# dlms_v1.net
KiCad netlist of a schematic drawn in EAGLE
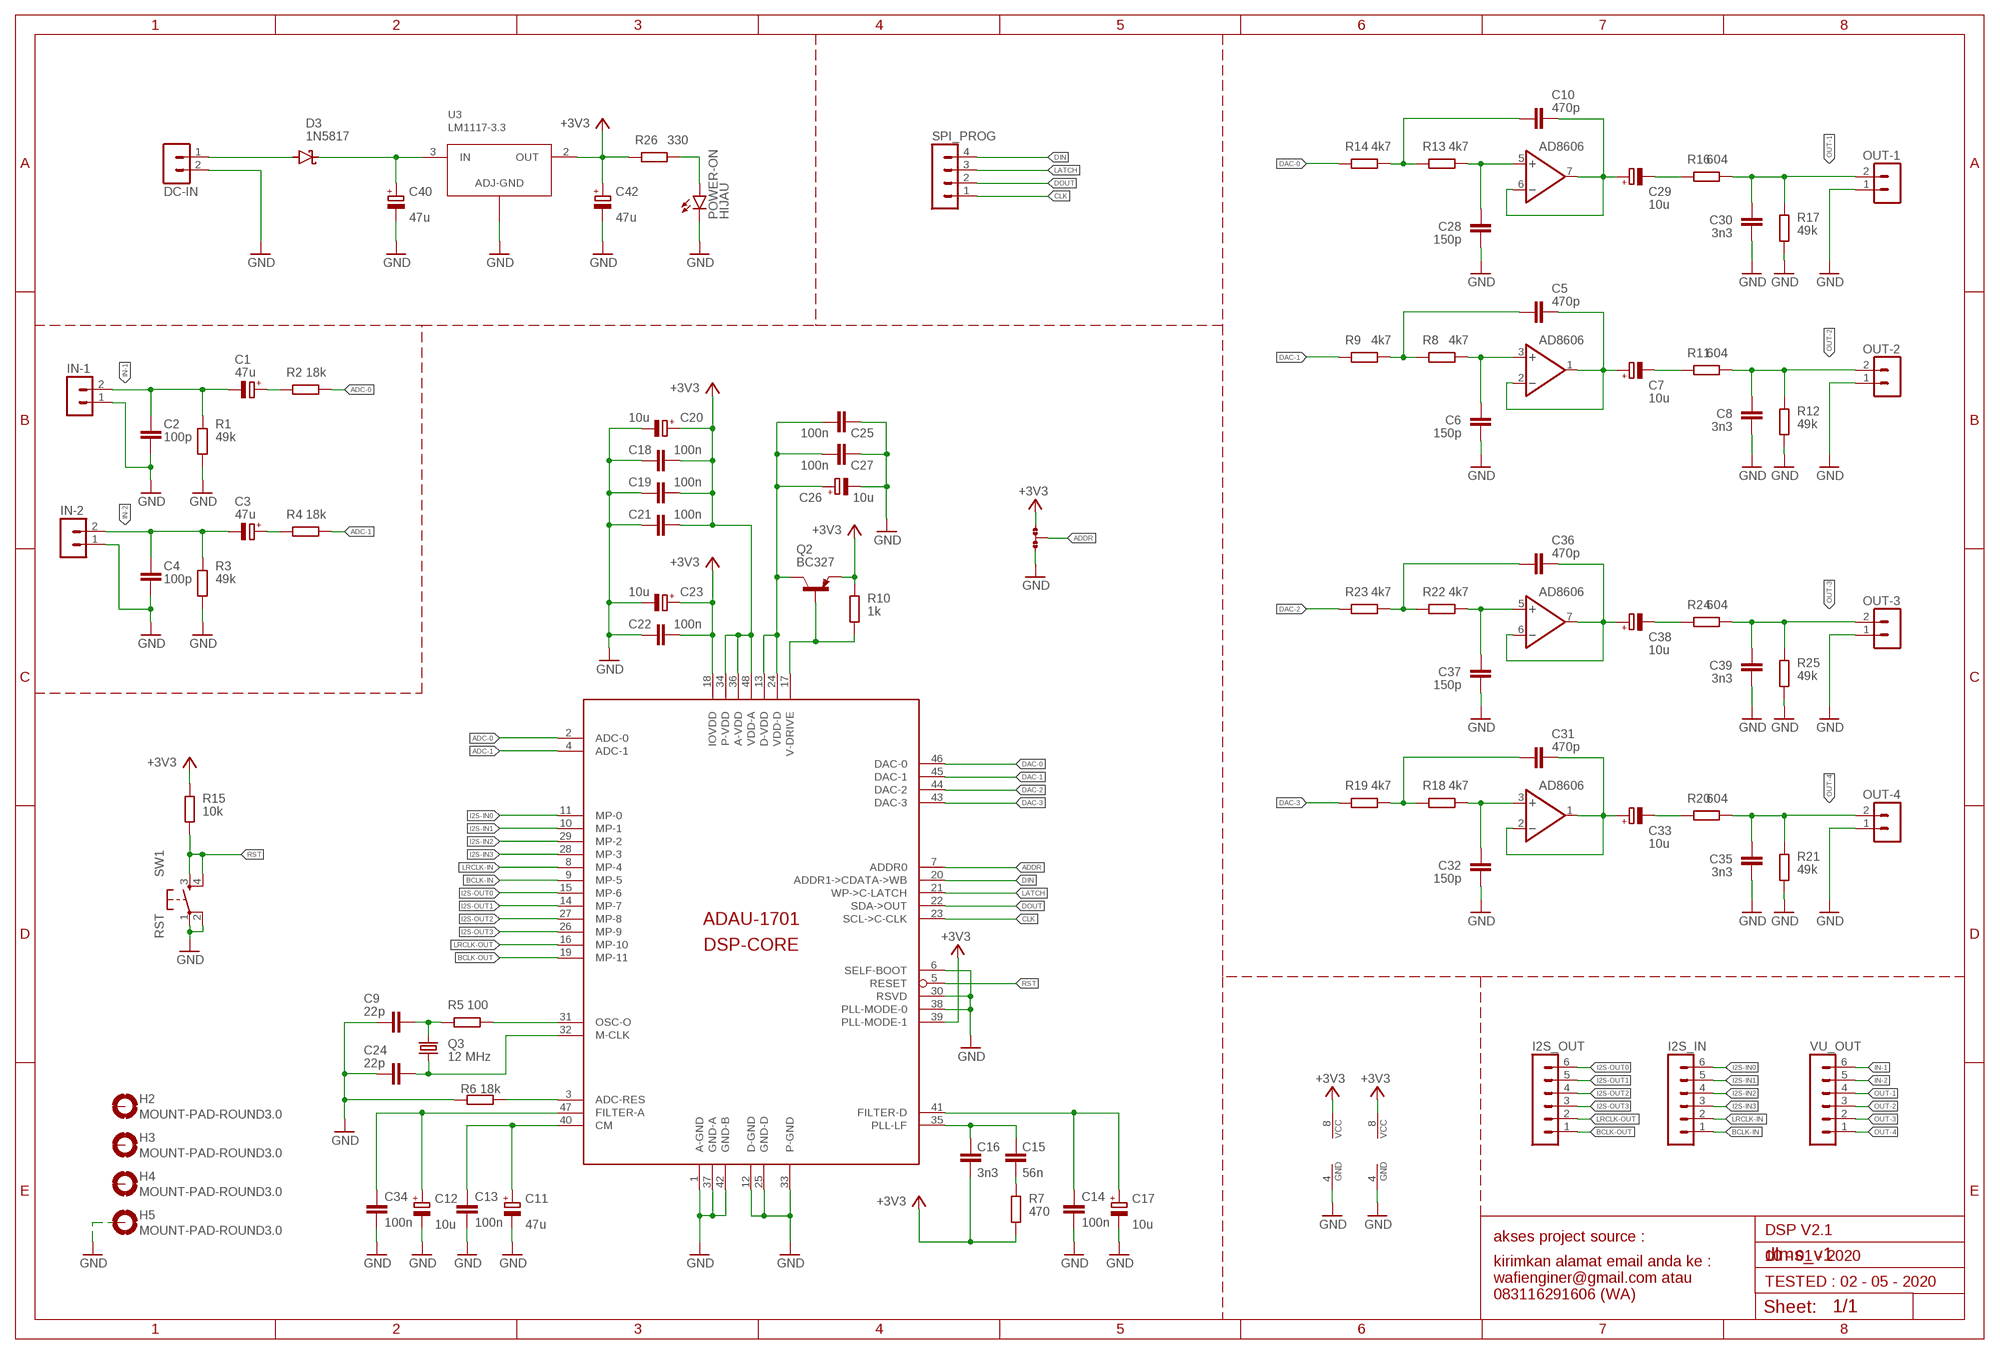
[diagram p0: schematic, sheet 1]

(export (version "E")
  (design (tool "Eeschema 10.0.6"))
  (components
    (comp (ref "ADDR")
      (value "0R-JUMPA")
      (footprint "eagle-import:A0R-JMP")
      (libsource (lib "eagle-import") (part "0R-JUMPA"))
    )
    (comp (ref "C1")
      (value "47u")
      (footprint "eagle-import:E2,5-5")
      (libsource (lib "eagle-import") (part "C10UF"))
    )
    (comp (ref "C2")
      (value "100p")
      (footprint "eagle-import:C050-024X044")
      (libsource (lib "eagle-import") (part "C-STD"))
    )
    (comp (ref "C3")
      (value "47u")
      (footprint "eagle-import:E2,5-5")
      (libsource (lib "eagle-import") (part "C10UF"))
    )
    (comp (ref "C4")
      (value "100p")
      (footprint "eagle-import:C050-024X044")
      (libsource (lib "eagle-import") (part "C-STD"))
    )
    (comp (ref "C5")
      (value "470p")
      (footprint "eagle-import:C050-024X044")
      (libsource (lib "eagle-import") (part "C-STD"))
    )
    (comp (ref "C6")
      (value "150p")
      (footprint "eagle-import:C050-024X044")
      (libsource (lib "eagle-import") (part "C-STD"))
    )
    (comp (ref "C7")
      (value "10u")
      (footprint "eagle-import:E2,5-5")
      (libsource (lib "eagle-import") (part "C10UF"))
    )
    (comp (ref "C8")
      (value "3n3")
      (footprint "eagle-import:C050-024X044")
      (libsource (lib "eagle-import") (part "C-STD"))
    )
    (comp (ref "C9")
      (value "22p")
      (footprint "eagle-import:0805")
      (libsource (lib "eagle-import") (part "CAP"))
    )
    (comp (ref "C10")
      (value "470p")
      (footprint "eagle-import:C050-024X044")
      (libsource (lib "eagle-import") (part "C-STD"))
    )
    (comp (ref "C11")
      (value "47u")
      (footprint "eagle-import:E2,5-5")
      (libsource (lib "eagle-import") (part "C10UF"))
    )
    (comp (ref "C12")
      (value "10u")
      (footprint "eagle-import:E2,5-5")
      (libsource (lib "eagle-import") (part "C10UF"))
    )
    (comp (ref "C13")
      (value "100n")
      (footprint "eagle-import:0805")
      (libsource (lib "eagle-import") (part "CAP"))
    )
    (comp (ref "C14")
      (value "100n")
      (footprint "eagle-import:0805")
      (libsource (lib "eagle-import") (part "CAP"))
    )
    (comp (ref "C15")
      (value "56n")
      (footprint "eagle-import:C050-024X044")
      (libsource (lib "eagle-import") (part "C-STD"))
    )
    (comp (ref "C16")
      (value "3n3")
      (footprint "eagle-import:C050-024X044")
      (libsource (lib "eagle-import") (part "C-STD"))
    )
    (comp (ref "C17")
      (value "10u")
      (footprint "eagle-import:E2,5-5")
      (libsource (lib "eagle-import") (part "C10UF"))
    )
    (comp (ref "C18")
      (value "100n")
      (footprint "eagle-import:0805")
      (libsource (lib "eagle-import") (part "CAP"))
    )
    (comp (ref "C19")
      (value "100n")
      (footprint "eagle-import:0805")
      (libsource (lib "eagle-import") (part "CAP"))
    )
    (comp (ref "C20")
      (value "10u")
      (footprint "eagle-import:E2,5-5")
      (libsource (lib "eagle-import") (part "C10UF"))
    )
    (comp (ref "C21")
      (value "100n")
      (footprint "eagle-import:0805")
      (libsource (lib "eagle-import") (part "CAP"))
    )
    (comp (ref "C22")
      (value "100n")
      (footprint "eagle-import:0805")
      (libsource (lib "eagle-import") (part "CAP"))
    )
    (comp (ref "C23")
      (value "10u")
      (footprint "eagle-import:E2,5-5")
      (libsource (lib "eagle-import") (part "C10UF"))
    )
    (comp (ref "C24")
      (value "22p")
      (footprint "eagle-import:0805")
      (libsource (lib "eagle-import") (part "CAP"))
    )
    (comp (ref "C25")
      (value "100n")
      (footprint "eagle-import:0805")
      (libsource (lib "eagle-import") (part "CAP"))
    )
    (comp (ref "C26")
      (value "10u")
      (footprint "eagle-import:E2,5-5")
      (libsource (lib "eagle-import") (part "C10UF"))
    )
    (comp (ref "C27")
      (value "100n")
      (footprint "eagle-import:0805")
      (libsource (lib "eagle-import") (part "CAP"))
    )
    (comp (ref "C28")
      (value "150p")
      (footprint "eagle-import:C050-024X044")
      (libsource (lib "eagle-import") (part "C-STD"))
    )
    (comp (ref "C29")
      (value "10u")
      (footprint "eagle-import:E2,5-5")
      (libsource (lib "eagle-import") (part "C10UF"))
    )
    (comp (ref "C30")
      (value "3n3")
      (footprint "eagle-import:C050-024X044")
      (libsource (lib "eagle-import") (part "C-STD"))
    )
    (comp (ref "C31")
      (value "470p")
      (footprint "eagle-import:C050-024X044")
      (libsource (lib "eagle-import") (part "C-STD"))
    )
    (comp (ref "C32")
      (value "150p")
      (footprint "eagle-import:C050-024X044")
      (libsource (lib "eagle-import") (part "C-STD"))
    )
    (comp (ref "C33")
      (value "10u")
      (footprint "eagle-import:E2,5-5")
      (libsource (lib "eagle-import") (part "C10UF"))
    )
    (comp (ref "C34")
      (value "100n")
      (footprint "eagle-import:0805")
      (libsource (lib "eagle-import") (part "CAP"))
    )
    (comp (ref "C35")
      (value "3n3")
      (footprint "eagle-import:C050-024X044")
      (libsource (lib "eagle-import") (part "C-STD"))
    )
    (comp (ref "C36")
      (value "470p")
      (footprint "eagle-import:C050-024X044")
      (libsource (lib "eagle-import") (part "C-STD"))
    )
    (comp (ref "C37")
      (value "150p")
      (footprint "eagle-import:C050-024X044")
      (libsource (lib "eagle-import") (part "C-STD"))
    )
    (comp (ref "C38")
      (value "10u")
      (footprint "eagle-import:E2,5-5")
      (libsource (lib "eagle-import") (part "C10UF"))
    )
    (comp (ref "C39")
      (value "3n3")
      (footprint "eagle-import:C050-024X044")
      (libsource (lib "eagle-import") (part "C-STD"))
    )
    (comp (ref "C40")
      (value "47u")
      (footprint "eagle-import:E2,5-5")
      (libsource (lib "eagle-import") (part "C10UF"))
    )
    (comp (ref "C42")
      (value "47u")
      (footprint "eagle-import:E2,5-5")
      (libsource (lib "eagle-import") (part "C10UF"))
    )
    (comp (ref "D3")
      (value "1N5817")
      (footprint "eagle-import:DO35Z7")
      (libsource (lib "eagle-import") (part "1N5817"))
    )
    (comp (ref "DC-IN")
      (value "MOLEX-2")
      (footprint "eagle-import:6410-02")
      (libsource (lib "eagle-import") (part "MOLEX-2"))
    )
    (comp (ref "H2")
      (value "MOUNT-PAD-ROUND3.0")
      (footprint "eagle-import:3,0-PAD")
      (libsource (lib "eagle-import") (part "MOUNT-PAD-ROUND3.0"))
    )
    (comp (ref "H3")
      (value "MOUNT-PAD-ROUND3.0")
      (footprint "eagle-import:3,0-PAD")
      (libsource (lib "eagle-import") (part "MOUNT-PAD-ROUND3.0"))
    )
    (comp (ref "H4")
      (value "MOUNT-PAD-ROUND3.0")
      (footprint "eagle-import:3,0-PAD")
      (libsource (lib "eagle-import") (part "MOUNT-PAD-ROUND3.0"))
    )
    (comp (ref "H5")
      (value "MOUNT-PAD-ROUND3.0")
      (footprint "eagle-import:3,0-PAD")
      (libsource (lib "eagle-import") (part "MOUNT-PAD-ROUND3.0"))
    )
    (comp (ref "I2S_IN")
      (value "MOLEX-6")
      (footprint "eagle-import:6410-06")
      (libsource (lib "eagle-import") (part "MOLEX-6"))
    )
    (comp (ref "I2S_OUT")
      (value "MOLEX-6")
      (footprint "eagle-import:6410-06")
      (libsource (lib "eagle-import") (part "MOLEX-6"))
    )
    (comp (ref "IC1")
      (value "AD8606")
      (footprint "eagle-import:SOP8")
      (libsource (lib "eagle-import") (part "AD8606"))
    )
    (comp (ref "IC2")
      (value "AD8606")
      (footprint "eagle-import:SOP8")
      (libsource (lib "eagle-import") (part "AD8606"))
    )
    (comp (ref "IN-1")
      (value "MOLEX-2")
      (footprint "eagle-import:6410-02")
      (libsource (lib "eagle-import") (part "MOLEX-2"))
    )
    (comp (ref "IN-2")
      (value "MOLEX-2")
      (footprint "eagle-import:6410-02")
      (libsource (lib "eagle-import") (part "MOLEX-2"))
    )
    (comp (ref "OUT-1")
      (value "MOLEX-2")
      (footprint "eagle-import:6410-02")
      (libsource (lib "eagle-import") (part "MOLEX-2"))
    )
    (comp (ref "OUT-2")
      (value "MOLEX-2")
      (footprint "eagle-import:6410-02")
      (libsource (lib "eagle-import") (part "MOLEX-2"))
    )
    (comp (ref "OUT-3")
      (value "MOLEX-2")
      (footprint "eagle-import:6410-02")
      (libsource (lib "eagle-import") (part "MOLEX-2"))
    )
    (comp (ref "OUT-4")
      (value "MOLEX-2")
      (footprint "eagle-import:6410-02")
      (libsource (lib "eagle-import") (part "MOLEX-2"))
    )
    (comp (ref "POWER-ON")
      (value "HIJAU")
      (footprint "eagle-import:LED3MM")
      (libsource (lib "eagle-import") (part "LED3MM"))
    )
    (comp (ref "Q2")
      (value "BC327")
      (footprint "eagle-import:TO92-EBC")
      (libsource (lib "eagle-import") (part "BC327"))
    )
    (comp (ref "Q3")
      (value "12 MHz")
      (footprint "eagle-import:HC49UP")
      (libsource (lib "eagle-import") (part "CRYSTALHC49UP"))
    )
    (comp (ref "R1")
      (value "49k")
      (footprint "eagle-import:0204_7")
      (libsource (lib "eagle-import") (part "R025"))
    )
    (comp (ref "R2")
      (value "18k")
      (footprint "eagle-import:0204_7")
      (libsource (lib "eagle-import") (part "R025"))
    )
    (comp (ref "R3")
      (value "49k")
      (footprint "eagle-import:0204_7")
      (libsource (lib "eagle-import") (part "R025"))
    )
    (comp (ref "R4")
      (value "18k")
      (footprint "eagle-import:0204_7")
      (libsource (lib "eagle-import") (part "R025"))
    )
    (comp (ref "R5")
      (value "100")
      (footprint "eagle-import:0204_7")
      (libsource (lib "eagle-import") (part "R025"))
    )
    (comp (ref "R6")
      (value "18k")
      (footprint "eagle-import:0204_7")
      (libsource (lib "eagle-import") (part "R025"))
    )
    (comp (ref "R7")
      (value "470")
      (footprint "eagle-import:0204_7")
      (libsource (lib "eagle-import") (part "R025"))
    )
    (comp (ref "R8")
      (value "4k7")
      (footprint "eagle-import:0204_7")
      (libsource (lib "eagle-import") (part "R025"))
    )
    (comp (ref "R9")
      (value "4k7")
      (footprint "eagle-import:0204_7")
      (libsource (lib "eagle-import") (part "R025"))
    )
    (comp (ref "R10")
      (value "1k")
      (footprint "eagle-import:0204_7")
      (libsource (lib "eagle-import") (part "R025"))
    )
    (comp (ref "R11")
      (value "604")
      (footprint "eagle-import:0204_7")
      (libsource (lib "eagle-import") (part "R025"))
    )
    (comp (ref "R12")
      (value "49k")
      (footprint "eagle-import:0204_7")
      (libsource (lib "eagle-import") (part "R025"))
    )
    (comp (ref "R13")
      (value "4k7")
      (footprint "eagle-import:0204_7")
      (libsource (lib "eagle-import") (part "R025"))
    )
    (comp (ref "R14")
      (value "4k7")
      (footprint "eagle-import:0204_7")
      (libsource (lib "eagle-import") (part "R025"))
    )
    (comp (ref "R15")
      (value "10k")
      (footprint "eagle-import:0204_7")
      (libsource (lib "eagle-import") (part "R025"))
    )
    (comp (ref "R16")
      (value "604")
      (footprint "eagle-import:0204_7")
      (libsource (lib "eagle-import") (part "R025"))
    )
    (comp (ref "R17")
      (value "49k")
      (footprint "eagle-import:0204_7")
      (libsource (lib "eagle-import") (part "R025"))
    )
    (comp (ref "R18")
      (value "4k7")
      (footprint "eagle-import:0204_7")
      (libsource (lib "eagle-import") (part "R025"))
    )
    (comp (ref "R19")
      (value "4k7")
      (footprint "eagle-import:0204_7")
      (libsource (lib "eagle-import") (part "R025"))
    )
    (comp (ref "R20")
      (value "604")
      (footprint "eagle-import:0204_7")
      (libsource (lib "eagle-import") (part "R025"))
    )
    (comp (ref "R21")
      (value "49k")
      (footprint "eagle-import:0204_7")
      (libsource (lib "eagle-import") (part "R025"))
    )
    (comp (ref "R22")
      (value "4k7")
      (footprint "eagle-import:0204_7")
      (libsource (lib "eagle-import") (part "R025"))
    )
    (comp (ref "R23")
      (value "4k7")
      (footprint "eagle-import:0204_7")
      (libsource (lib "eagle-import") (part "R025"))
    )
    (comp (ref "R24")
      (value "604")
      (footprint "eagle-import:0204_7")
      (libsource (lib "eagle-import") (part "R025"))
    )
    (comp (ref "R25")
      (value "49k")
      (footprint "eagle-import:0204_7")
      (libsource (lib "eagle-import") (part "R025"))
    )
    (comp (ref "R26")
      (value "330")
      (footprint "eagle-import:0204_7")
      (libsource (lib "eagle-import") (part "R025"))
    )
    (comp (ref "RST")
      (value "SW1")
      (footprint "eagle-import:B3F-10XX")
      (libsource (lib "eagle-import") (part "SW"))
    )
    (comp (ref "SPI_PROG")
      (value "MOLEX-4")
      (footprint "eagle-import:6410-04")
      (libsource (lib "eagle-import") (part "MOLEX-4"))
    )
    (comp (ref "U1")
      (value "ADAU-1701")
      (footprint "eagle-import:LQFP-48")
      (libsource (lib "eagle-import") (part "ADAU-1701"))
    )
    (comp (ref "U3")
      (value "LM1117-3.3")
      (footprint "eagle-import:TO220H")
      (libsource (lib "eagle-import") (part "LM1117-3.3"))
    )
    (comp (ref "VU_OUT")
      (value "MOLEX-6")
      (footprint "eagle-import:6410-06")
      (libsource (lib "eagle-import") (part "MOLEX-6"))
    )
  )
  (nets
    (net (code "1") (name "+3V3") (class "Default")
      (node (ref "ADDR") (pin "1") (pinfunction "1_1") (pintype "passive"))
      (node (ref "C16") (pin "2") (pinfunction "2_2") (pintype "passive"))
      (node (ref "C18") (pin "P$1") (pinfunction "1_P$1") (pintype "passive"))
      (node (ref "C19") (pin "P$1") (pinfunction "1_P$1") (pintype "passive"))
      (node (ref "C20") (pin "+") (pinfunction "+_+") (pintype "passive"))
      (node (ref "C21") (pin "P$1") (pinfunction "1_P$1") (pintype "passive"))
      (node (ref "C22") (pin "P$1") (pinfunction "1_P$1") (pintype "passive"))
      (node (ref "C23") (pin "+") (pinfunction "+_+") (pintype "passive"))
      (node (ref "C42") (pin "+") (pinfunction "+_+") (pintype "passive"))
      (node (ref "IC1") (pin "8") (pinfunction "VCC_8") (pintype "power_in"))
      (node (ref "IC2") (pin "8") (pinfunction "VCC_8") (pintype "power_in"))
      (node (ref "Q2") (pin "E") (pinfunction "E_E") (pintype "passive"))
      (node (ref "R10") (pin "2") (pinfunction "2_2") (pintype "passive"))
      (node (ref "R15") (pin "2") (pinfunction "2_2") (pintype "passive"))
      (node (ref "R26") (pin "1") (pinfunction "1_1") (pintype "passive"))
      (node (ref "R7") (pin "1") (pinfunction "1_1") (pintype "passive"))
      (node (ref "U1") (pin "18") (pinfunction "IOVDD_18") (pintype "bidirectional"))
      (node (ref "U1") (pin "34") (pinfunction "P-VDD_34") (pintype "bidirectional"))
      (node (ref "U1") (pin "36") (pinfunction "A-VDD_36") (pintype "bidirectional"))
      (node (ref "U1") (pin "39") (pinfunction "PLL-MODE-1_39") (pintype "bidirectional"))
      (node (ref "U1") (pin "48") (pinfunction "VDD-A_48") (pintype "bidirectional"))
      (node (ref "U3") (pin "2") (pinfunction "OUT_2") (pintype "bidirectional"))
    )
    (net (code "2") (name "ADC-0") (class "Default")
      (node (ref "R2") (pin "2") (pinfunction "2_2") (pintype "passive"))
      (node (ref "U1") (pin "2") (pinfunction "ADC-0_2") (pintype "bidirectional"))
    )
    (net (code "3") (name "ADC-1") (class "Default")
      (node (ref "R4") (pin "2") (pinfunction "2_2") (pintype "passive"))
      (node (ref "U1") (pin "4") (pinfunction "ADC-1_4") (pintype "bidirectional"))
    )
    (net (code "4") (name "ADDR") (class "Default")
      (node (ref "ADDR") (pin "2") (pinfunction "2_2") (pintype "passive"))
      (node (ref "U1") (pin "7") (pinfunction "ADDR0_7") (pintype "bidirectional"))
    )
    (net (code "5") (name "BCLK-IN") (class "Default")
      (node (ref "I2S_IN") (pin "1") (pinfunction "1_1") (pintype "passive"))
      (node (ref "U1") (pin "9") (pinfunction "MP-5_9") (pintype "bidirectional"))
    )
    (net (code "6") (name "BCLK-OUT") (class "Default")
      (node (ref "I2S_OUT") (pin "1") (pinfunction "1_1") (pintype "passive"))
      (node (ref "U1") (pin "19") (pinfunction "MP-11_19") (pintype "bidirectional"))
    )
    (net (code "7") (name "CLK") (class "Default")
      (node (ref "SPI_PROG") (pin "1") (pinfunction "1_1") (pintype "passive"))
      (node (ref "U1") (pin "23") (pinfunction "SCL->C-CLK_23") (pintype "bidirectional"))
    )
    (net (code "8") (name "DAC-0") (class "Default")
      (node (ref "R14") (pin "1") (pinfunction "1_1") (pintype "passive"))
      (node (ref "U1") (pin "46") (pinfunction "DAC-0_46") (pintype "bidirectional"))
    )
    (net (code "9") (name "DAC-1") (class "Default")
      (node (ref "R9") (pin "1") (pinfunction "1_1") (pintype "passive"))
      (node (ref "U1") (pin "45") (pinfunction "DAC-1_45") (pintype "bidirectional"))
    )
    (net (code "10") (name "DAC-2") (class "Default")
      (node (ref "R23") (pin "1") (pinfunction "1_1") (pintype "passive"))
      (node (ref "U1") (pin "44") (pinfunction "DAC-2_44") (pintype "bidirectional"))
    )
    (net (code "11") (name "DAC-3") (class "Default")
      (node (ref "R19") (pin "1") (pinfunction "1_1") (pintype "passive"))
      (node (ref "U1") (pin "43") (pinfunction "DAC-3_43") (pintype "bidirectional"))
    )
    (net (code "12") (name "DIN") (class "Default")
      (node (ref "SPI_PROG") (pin "4") (pinfunction "4_4") (pintype "passive"))
      (node (ref "U1") (pin "20") (pinfunction "ADDR1->CDATA->WB_20") (pintype "bidirectional"))
    )
    (net (code "13") (name "DOUT") (class "Default")
      (node (ref "SPI_PROG") (pin "2") (pinfunction "2_2") (pintype "passive"))
      (node (ref "U1") (pin "22") (pinfunction "SDA->OUT_22") (pintype "bidirectional"))
    )
    (net (code "14") (name "GND") (class "Default")
      (node (ref "ADDR") (pin "3") (pinfunction "3_3") (pintype "passive"))
      (node (ref "C11") (pin "-") (pinfunction "-_-") (pintype "passive"))
      (node (ref "C12") (pin "-") (pinfunction "-_-") (pintype "passive"))
      (node (ref "C13") (pin "P$2") (pinfunction "2_P$2") (pintype "passive"))
      (node (ref "C14") (pin "P$2") (pinfunction "2_P$2") (pintype "passive"))
      (node (ref "C17") (pin "-") (pinfunction "-_-") (pintype "passive"))
      (node (ref "C18") (pin "P$2") (pinfunction "2_P$2") (pintype "passive"))
      (node (ref "C19") (pin "P$2") (pinfunction "2_P$2") (pintype "passive"))
      (node (ref "C2") (pin "2") (pinfunction "2_2") (pintype "passive"))
      (node (ref "C20") (pin "-") (pinfunction "-_-") (pintype "passive"))
      (node (ref "C21") (pin "P$2") (pinfunction "2_P$2") (pintype "passive"))
      (node (ref "C22") (pin "P$2") (pinfunction "2_P$2") (pintype "passive"))
      (node (ref "C23") (pin "-") (pinfunction "-_-") (pintype "passive"))
      (node (ref "C24") (pin "P$2") (pinfunction "2_P$2") (pintype "passive"))
      (node (ref "C25") (pin "P$2") (pinfunction "2_P$2") (pintype "passive"))
      (node (ref "C26") (pin "-") (pinfunction "-_-") (pintype "passive"))
      (node (ref "C27") (pin "P$2") (pinfunction "2_P$2") (pintype "passive"))
      (node (ref "C28") (pin "1") (pinfunction "1_1") (pintype "passive"))
      (node (ref "C30") (pin "2") (pinfunction "2_2") (pintype "passive"))
      (node (ref "C32") (pin "1") (pinfunction "1_1") (pintype "passive"))
      (node (ref "C34") (pin "P$2") (pinfunction "2_P$2") (pintype "passive"))
      (node (ref "C35") (pin "2") (pinfunction "2_2") (pintype "passive"))
      (node (ref "C37") (pin "1") (pinfunction "1_1") (pintype "passive"))
      (node (ref "C39") (pin "2") (pinfunction "2_2") (pintype "passive"))
      (node (ref "C4") (pin "2") (pinfunction "2_2") (pintype "passive"))
      (node (ref "C40") (pin "-") (pinfunction "-_-") (pintype "passive"))
      (node (ref "C42") (pin "-") (pinfunction "-_-") (pintype "passive"))
      (node (ref "C6") (pin "1") (pinfunction "1_1") (pintype "passive"))
      (node (ref "C8") (pin "2") (pinfunction "2_2") (pintype "passive"))
      (node (ref "C9") (pin "P$2") (pinfunction "2_P$2") (pintype "passive"))
      (node (ref "DC-IN") (pin "2") (pinfunction "2_2") (pintype "passive"))
      (node (ref "H5") (pin "B3,0") (pinfunction "MOUNT_B3,0") (pintype "passive"))
      (node (ref "IC1") (pin "4") (pinfunction "GND_4") (pintype "power_in"))
      (node (ref "IC2") (pin "4") (pinfunction "GND_4") (pintype "power_in"))
      (node (ref "IN-1") (pin "1") (pinfunction "1_1") (pintype "passive"))
      (node (ref "IN-2") (pin "1") (pinfunction "1_1") (pintype "passive"))
      (node (ref "OUT-1") (pin "1") (pinfunction "1_1") (pintype "passive"))
      (node (ref "OUT-2") (pin "1") (pinfunction "1_1") (pintype "passive"))
      (node (ref "OUT-3") (pin "1") (pinfunction "1_1") (pintype "passive"))
      (node (ref "OUT-4") (pin "1") (pinfunction "1_1") (pintype "passive"))
      (node (ref "POWER-ON") (pin "K") (pinfunction "C_K") (pintype "passive"))
      (node (ref "R1") (pin "1") (pinfunction "1_1") (pintype "passive"))
      (node (ref "R12") (pin "1") (pinfunction "1_1") (pintype "passive"))
      (node (ref "R17") (pin "1") (pinfunction "1_1") (pintype "passive"))
      (node (ref "R21") (pin "1") (pinfunction "1_1") (pintype "passive"))
      (node (ref "R25") (pin "1") (pinfunction "1_1") (pintype "passive"))
      (node (ref "R3") (pin "1") (pinfunction "1_1") (pintype "passive"))
      (node (ref "R6") (pin "1") (pinfunction "1_1") (pintype "passive"))
      (node (ref "RST") (pin "1") (pinfunction "P_1") (pintype "passive"))
      (node (ref "RST") (pin "2") (pinfunction "P1_2") (pintype "passive"))
      (node (ref "U1") (pin "1") (pinfunction "A-GND_1") (pintype "bidirectional"))
      (node (ref "U1") (pin "12") (pinfunction "D-GND_12") (pintype "bidirectional"))
      (node (ref "U1") (pin "25") (pinfunction "GND-D_25") (pintype "bidirectional"))
      (node (ref "U1") (pin "30") (pinfunction "RSVD_30") (pintype "bidirectional"))
      (node (ref "U1") (pin "33") (pinfunction "P-GND_33") (pintype "bidirectional"))
      (node (ref "U1") (pin "37") (pinfunction "GND-A_37") (pintype "bidirectional"))
      (node (ref "U1") (pin "38") (pinfunction "PLL-MODE-0_38") (pintype "bidirectional"))
      (node (ref "U1") (pin "42") (pinfunction "GND-B_42") (pintype "bidirectional"))
      (node (ref "U1") (pin "6") (pinfunction "SELF-BOOT_6") (pintype "bidirectional"))
      (node (ref "U3") (pin "1") (pinfunction "GND_1") (pintype "bidirectional"))
    )
    (net (code "15") (name "I2S-IN0") (class "Default")
      (node (ref "I2S_IN") (pin "6") (pinfunction "6_6") (pintype "passive"))
      (node (ref "U1") (pin "11") (pinfunction "MP-0_11") (pintype "bidirectional"))
    )
    (net (code "16") (name "I2S-IN1") (class "Default")
      (node (ref "I2S_IN") (pin "5") (pinfunction "5_5") (pintype "passive"))
      (node (ref "U1") (pin "10") (pinfunction "MP-1_10") (pintype "bidirectional"))
    )
    (net (code "17") (name "I2S-IN2") (class "Default")
      (node (ref "I2S_IN") (pin "4") (pinfunction "4_4") (pintype "passive"))
      (node (ref "U1") (pin "29") (pinfunction "MP-2_29") (pintype "bidirectional"))
    )
    (net (code "18") (name "I2S-IN3") (class "Default")
      (node (ref "I2S_IN") (pin "3") (pinfunction "3_3") (pintype "passive"))
      (node (ref "U1") (pin "28") (pinfunction "MP-3_28") (pintype "bidirectional"))
    )
    (net (code "19") (name "I2S-OUT0") (class "Default")
      (node (ref "I2S_OUT") (pin "6") (pinfunction "6_6") (pintype "passive"))
      (node (ref "U1") (pin "15") (pinfunction "MP-6_15") (pintype "bidirectional"))
    )
    (net (code "20") (name "I2S-OUT1") (class "Default")
      (node (ref "I2S_OUT") (pin "5") (pinfunction "5_5") (pintype "passive"))
      (node (ref "U1") (pin "14") (pinfunction "MP-7_14") (pintype "bidirectional"))
    )
    (net (code "21") (name "I2S-OUT2") (class "Default")
      (node (ref "I2S_OUT") (pin "4") (pinfunction "4_4") (pintype "passive"))
      (node (ref "U1") (pin "27") (pinfunction "MP-8_27") (pintype "bidirectional"))
    )
    (net (code "22") (name "I2S-OUT3") (class "Default")
      (node (ref "I2S_OUT") (pin "3") (pinfunction "3_3") (pintype "passive"))
      (node (ref "U1") (pin "26") (pinfunction "MP-9_26") (pintype "bidirectional"))
    )
    (net (code "23") (name "IN-1") (class "Default")
      (node (ref "C1") (pin "-") (pinfunction "-_-") (pintype "passive"))
      (node (ref "C2") (pin "1") (pinfunction "1_1") (pintype "passive"))
      (node (ref "IN-1") (pin "2") (pinfunction "2_2") (pintype "passive"))
      (node (ref "R1") (pin "2") (pinfunction "2_2") (pintype "passive"))
      (node (ref "VU_OUT") (pin "6") (pinfunction "6_6") (pintype "passive"))
    )
    (net (code "24") (name "IN-2") (class "Default")
      (node (ref "C3") (pin "-") (pinfunction "-_-") (pintype "passive"))
      (node (ref "C4") (pin "1") (pinfunction "1_1") (pintype "passive"))
      (node (ref "IN-2") (pin "2") (pinfunction "2_2") (pintype "passive"))
      (node (ref "R3") (pin "2") (pinfunction "2_2") (pintype "passive"))
      (node (ref "VU_OUT") (pin "5") (pinfunction "5_5") (pintype "passive"))
    )
    (net (code "25") (name "LATCH") (class "Default")
      (node (ref "SPI_PROG") (pin "3") (pinfunction "3_3") (pintype "passive"))
      (node (ref "U1") (pin "21") (pinfunction "WP->C-LATCH_21") (pintype "bidirectional"))
    )
    (net (code "26") (name "LRCLK-IN") (class "Default")
      (node (ref "I2S_IN") (pin "2") (pinfunction "2_2") (pintype "passive"))
      (node (ref "U1") (pin "8") (pinfunction "MP-4_8") (pintype "bidirectional"))
    )
    (net (code "27") (name "LRCLK-OUT") (class "Default")
      (node (ref "I2S_OUT") (pin "2") (pinfunction "2_2") (pintype "passive"))
      (node (ref "U1") (pin "16") (pinfunction "MP-10_16") (pintype "bidirectional"))
    )
    (net (code "28") (name "Net-(C1-Pad+)") (class "Default")
      (node (ref "C1") (pin "+") (pinfunction "+_+") (pintype "passive"))
      (node (ref "R2") (pin "1") (pinfunction "1_1") (pintype "passive"))
    )
    (net (code "29") (name "Net-(C3-Pad+)") (class "Default")
      (node (ref "C3") (pin "+") (pinfunction "+_+") (pintype "passive"))
      (node (ref "R4") (pin "1") (pinfunction "1_1") (pintype "passive"))
    )
    (net (code "30") (name "Net-(C5-Pad1)") (class "Default")
      (node (ref "C5") (pin "1") (pinfunction "1_1") (pintype "passive"))
      (node (ref "R8") (pin "1") (pinfunction "1_1") (pintype "passive"))
      (node (ref "R9") (pin "2") (pinfunction "2_2") (pintype "passive"))
    )
    (net (code "31") (name "Net-(C7-Pad-)") (class "Default")
      (node (ref "C7") (pin "-") (pinfunction "-_-") (pintype "passive"))
      (node (ref "R11") (pin "1") (pinfunction "1_1") (pintype "passive"))
    )
    (net (code "32") (name "Net-(C9-1)") (class "Default")
      (node (ref "C9") (pin "P$1") (pinfunction "1_P$1") (pintype "passive"))
      (node (ref "Q3") (pin "2") (pinfunction "2_2") (pintype "passive"))
      (node (ref "R5") (pin "1") (pinfunction "1_1") (pintype "passive"))
    )
    (net (code "33") (name "Net-(C10-Pad1)") (class "Default")
      (node (ref "C10") (pin "1") (pinfunction "1_1") (pintype "passive"))
      (node (ref "R13") (pin "1") (pinfunction "1_1") (pintype "passive"))
      (node (ref "R14") (pin "2") (pinfunction "2_2") (pintype "passive"))
    )
    (net (code "34") (name "Net-(C13-1)") (class "Default")
      (node (ref "C11") (pin "+") (pinfunction "+_+") (pintype "passive"))
      (node (ref "C13") (pin "P$1") (pinfunction "1_P$1") (pintype "passive"))
      (node (ref "U1") (pin "40") (pinfunction "CM_40") (pintype "bidirectional"))
    )
    (net (code "35") (name "Net-(C14-1)") (class "Default")
      (node (ref "C14") (pin "P$1") (pinfunction "1_P$1") (pintype "passive"))
      (node (ref "C17") (pin "+") (pinfunction "+_+") (pintype "passive"))
      (node (ref "U1") (pin "41") (pinfunction "FILTER-D_41") (pintype "bidirectional"))
    )
    (net (code "36") (name "Net-(C15-Pad2)") (class "Default")
      (node (ref "C15") (pin "2") (pinfunction "2_2") (pintype "passive"))
      (node (ref "R7") (pin "2") (pinfunction "2_2") (pintype "passive"))
    )
    (net (code "37") (name "Net-(C24-1)") (class "Default")
      (node (ref "C24") (pin "P$1") (pinfunction "1_P$1") (pintype "passive"))
      (node (ref "Q3") (pin "1") (pinfunction "1_1") (pintype "passive"))
      (node (ref "U1") (pin "32") (pinfunction "M-CLK_32") (pintype "bidirectional"))
    )
    (net (code "38") (name "Net-(C25-1)") (class "Default")
      (node (ref "C25") (pin "P$1") (pinfunction "1_P$1") (pintype "passive"))
      (node (ref "C26") (pin "+") (pinfunction "+_+") (pintype "passive"))
      (node (ref "C27") (pin "P$1") (pinfunction "1_P$1") (pintype "passive"))
      (node (ref "Q2") (pin "C") (pinfunction "C_C") (pintype "passive"))
      (node (ref "U1") (pin "13") (pinfunction "D-VDD_13") (pintype "bidirectional"))
      (node (ref "U1") (pin "24") (pinfunction "VDD-D_24") (pintype "bidirectional"))
    )
    (net (code "39") (name "Net-(C29-Pad-)") (class "Default")
      (node (ref "C29") (pin "-") (pinfunction "-_-") (pintype "passive"))
      (node (ref "R16") (pin "1") (pinfunction "1_1") (pintype "passive"))
    )
    (net (code "40") (name "Net-(C31-Pad1)") (class "Default")
      (node (ref "C31") (pin "1") (pinfunction "1_1") (pintype "passive"))
      (node (ref "R18") (pin "1") (pinfunction "1_1") (pintype "passive"))
      (node (ref "R19") (pin "2") (pinfunction "2_2") (pintype "passive"))
    )
    (net (code "41") (name "Net-(C33-Pad-)") (class "Default")
      (node (ref "C33") (pin "-") (pinfunction "-_-") (pintype "passive"))
      (node (ref "R20") (pin "1") (pinfunction "1_1") (pintype "passive"))
    )
    (net (code "42") (name "Net-(C34-1)") (class "Default")
      (node (ref "C12") (pin "+") (pinfunction "+_+") (pintype "passive"))
      (node (ref "C34") (pin "P$1") (pinfunction "1_P$1") (pintype "passive"))
      (node (ref "U1") (pin "47") (pinfunction "FILTER-A_47") (pintype "bidirectional"))
    )
    (net (code "43") (name "Net-(C36-Pad1)") (class "Default")
      (node (ref "C36") (pin "1") (pinfunction "1_1") (pintype "passive"))
      (node (ref "R22") (pin "1") (pinfunction "1_1") (pintype "passive"))
      (node (ref "R23") (pin "2") (pinfunction "2_2") (pintype "passive"))
    )
    (net (code "44") (name "Net-(C38-Pad-)") (class "Default")
      (node (ref "C38") (pin "-") (pinfunction "-_-") (pintype "passive"))
      (node (ref "R24") (pin "1") (pinfunction "1_1") (pintype "passive"))
    )
    (net (code "45") (name "Net-(D3-PadA)") (class "Default")
      (node (ref "D3") (pin "A") (pinfunction "A_A") (pintype "passive"))
      (node (ref "DC-IN") (pin "1") (pinfunction "1_1") (pintype "passive"))
    )
    (net (code "46") (name "Net-(IC1A-+IN)") (class "Default")
      (node (ref "C6") (pin "2") (pinfunction "2_2") (pintype "passive"))
      (node (ref "IC1") (pin "3") (pinfunction "+IN_3") (pintype "input"))
      (node (ref "R8") (pin "2") (pinfunction "2_2") (pintype "passive"))
    )
    (net (code "47") (name "Net-(IC1A--IN)") (class "Default")
      (node (ref "C5") (pin "2") (pinfunction "2_2") (pintype "passive"))
      (node (ref "C7") (pin "+") (pinfunction "+_+") (pintype "passive"))
      (node (ref "IC1") (pin "1") (pinfunction "OUT_1") (pintype "output"))
      (node (ref "IC1") (pin "2") (pinfunction "-IN_2") (pintype "input"))
    )
    (net (code "48") (name "Net-(IC1B-+IN)") (class "Default")
      (node (ref "C28") (pin "2") (pinfunction "2_2") (pintype "passive"))
      (node (ref "IC1") (pin "5") (pinfunction "+IN_5") (pintype "input"))
      (node (ref "R13") (pin "2") (pinfunction "2_2") (pintype "passive"))
    )
    (net (code "49") (name "Net-(IC1B--IN)") (class "Default")
      (node (ref "C10") (pin "2") (pinfunction "2_2") (pintype "passive"))
      (node (ref "C29") (pin "+") (pinfunction "+_+") (pintype "passive"))
      (node (ref "IC1") (pin "6") (pinfunction "-IN_6") (pintype "input"))
      (node (ref "IC1") (pin "7") (pinfunction "OUT_7") (pintype "output"))
    )
    (net (code "50") (name "Net-(IC2A-+IN)") (class "Default")
      (node (ref "C32") (pin "2") (pinfunction "2_2") (pintype "passive"))
      (node (ref "IC2") (pin "3") (pinfunction "+IN_3") (pintype "input"))
      (node (ref "R18") (pin "2") (pinfunction "2_2") (pintype "passive"))
    )
    (net (code "51") (name "Net-(IC2A--IN)") (class "Default")
      (node (ref "C31") (pin "2") (pinfunction "2_2") (pintype "passive"))
      (node (ref "C33") (pin "+") (pinfunction "+_+") (pintype "passive"))
      (node (ref "IC2") (pin "1") (pinfunction "OUT_1") (pintype "output"))
      (node (ref "IC2") (pin "2") (pinfunction "-IN_2") (pintype "input"))
    )
    (net (code "52") (name "Net-(IC2B-+IN)") (class "Default")
      (node (ref "C37") (pin "2") (pinfunction "2_2") (pintype "passive"))
      (node (ref "IC2") (pin "5") (pinfunction "+IN_5") (pintype "input"))
      (node (ref "R22") (pin "2") (pinfunction "2_2") (pintype "passive"))
    )
    (net (code "53") (name "Net-(IC2B--IN)") (class "Default")
      (node (ref "C36") (pin "2") (pinfunction "2_2") (pintype "passive"))
      (node (ref "C38") (pin "+") (pinfunction "+_+") (pintype "passive"))
      (node (ref "IC2") (pin "6") (pinfunction "-IN_6") (pintype "input"))
      (node (ref "IC2") (pin "7") (pinfunction "OUT_7") (pintype "output"))
    )
    (net (code "54") (name "Net-(POWER-ON-PadA)") (class "Default")
      (node (ref "POWER-ON") (pin "A") (pinfunction "A_A") (pintype "passive"))
      (node (ref "R26") (pin "2") (pinfunction "2_2") (pintype "passive"))
    )
    (net (code "55") (name "Net-(U1-ADC-RES)") (class "Default")
      (node (ref "R6") (pin "2") (pinfunction "2_2") (pintype "passive"))
      (node (ref "U1") (pin "3") (pinfunction "ADC-RES_3") (pintype "bidirectional"))
    )
    (net (code "56") (name "Net-(U1-OSC-O)") (class "Default")
      (node (ref "R5") (pin "2") (pinfunction "2_2") (pintype "passive"))
      (node (ref "U1") (pin "31") (pinfunction "OSC-O_31") (pintype "bidirectional"))
    )
    (net (code "57") (name "Net-(U1-PLL-LF)") (class "Default")
      (node (ref "C15") (pin "1") (pinfunction "1_1") (pintype "passive"))
      (node (ref "C16") (pin "1") (pinfunction "1_1") (pintype "passive"))
      (node (ref "U1") (pin "35") (pinfunction "PLL-LF_35") (pintype "bidirectional"))
    )
    (net (code "58") (name "Net-(U1-V-DRIVE)") (class "Default")
      (node (ref "Q2") (pin "B") (pinfunction "B_B") (pintype "passive"))
      (node (ref "R10") (pin "1") (pinfunction "1_1") (pintype "passive"))
      (node (ref "U1") (pin "17") (pinfunction "V-DRIVE_17") (pintype "bidirectional"))
    )
    (net (code "59") (name "Net-(U3-IN)") (class "Default")
      (node (ref "C40") (pin "+") (pinfunction "+_+") (pintype "passive"))
      (node (ref "D3") (pin "C") (pinfunction "C_C") (pintype "passive"))
      (node (ref "U3") (pin "3") (pinfunction "IN_3") (pintype "bidirectional"))
    )
    (net (code "60") (name "OUT-1") (class "Default")
      (node (ref "C30") (pin "1") (pinfunction "1_1") (pintype "passive"))
      (node (ref "OUT-1") (pin "2") (pinfunction "2_2") (pintype "passive"))
      (node (ref "R16") (pin "2") (pinfunction "2_2") (pintype "passive"))
      (node (ref "R17") (pin "2") (pinfunction "2_2") (pintype "passive"))
      (node (ref "VU_OUT") (pin "4") (pinfunction "4_4") (pintype "passive"))
    )
    (net (code "61") (name "OUT-2") (class "Default")
      (node (ref "C8") (pin "1") (pinfunction "1_1") (pintype "passive"))
      (node (ref "OUT-2") (pin "2") (pinfunction "2_2") (pintype "passive"))
      (node (ref "R11") (pin "2") (pinfunction "2_2") (pintype "passive"))
      (node (ref "R12") (pin "2") (pinfunction "2_2") (pintype "passive"))
      (node (ref "VU_OUT") (pin "3") (pinfunction "3_3") (pintype "passive"))
    )
    (net (code "62") (name "OUT-3") (class "Default")
      (node (ref "C39") (pin "1") (pinfunction "1_1") (pintype "passive"))
      (node (ref "OUT-3") (pin "2") (pinfunction "2_2") (pintype "passive"))
      (node (ref "R24") (pin "2") (pinfunction "2_2") (pintype "passive"))
      (node (ref "R25") (pin "2") (pinfunction "2_2") (pintype "passive"))
      (node (ref "VU_OUT") (pin "2") (pinfunction "2_2") (pintype "passive"))
    )
    (net (code "63") (name "OUT-4") (class "Default")
      (node (ref "C35") (pin "1") (pinfunction "1_1") (pintype "passive"))
      (node (ref "OUT-4") (pin "2") (pinfunction "2_2") (pintype "passive"))
      (node (ref "R20") (pin "2") (pinfunction "2_2") (pintype "passive"))
      (node (ref "R21") (pin "2") (pinfunction "2_2") (pintype "passive"))
      (node (ref "VU_OUT") (pin "1") (pinfunction "1_1") (pintype "passive"))
    )
    (net (code "64") (name "RST") (class "Default")
      (node (ref "R15") (pin "1") (pinfunction "1_1") (pintype "passive"))
      (node (ref "RST") (pin "3") (pinfunction "S_3") (pintype "passive"))
      (node (ref "RST") (pin "4") (pinfunction "S1_4") (pintype "passive"))
      (node (ref "U1") (pin "5") (pinfunction "RESET_5") (pintype "bidirectional"))
    )
    (net (code "65") (name "unconnected-(H2-MOUNT-PadB3,0)") (class "Default")
      (node (ref "H2") (pin "B3,0") (pinfunction "MOUNT_B3,0") (pintype "passive"))
    )
    (net (code "66") (name "unconnected-(H3-MOUNT-PadB3,0)") (class "Default")
      (node (ref "H3") (pin "B3,0") (pinfunction "MOUNT_B3,0") (pintype "passive"))
    )
    (net (code "67") (name "unconnected-(H4-MOUNT-PadB3,0)") (class "Default")
      (node (ref "H4") (pin "B3,0") (pinfunction "MOUNT_B3,0") (pintype "passive"))
    )
  )
)
